# Pro_Trinket_Keyboard.net
KiCad netlist of a schematic drawn in EAGLE
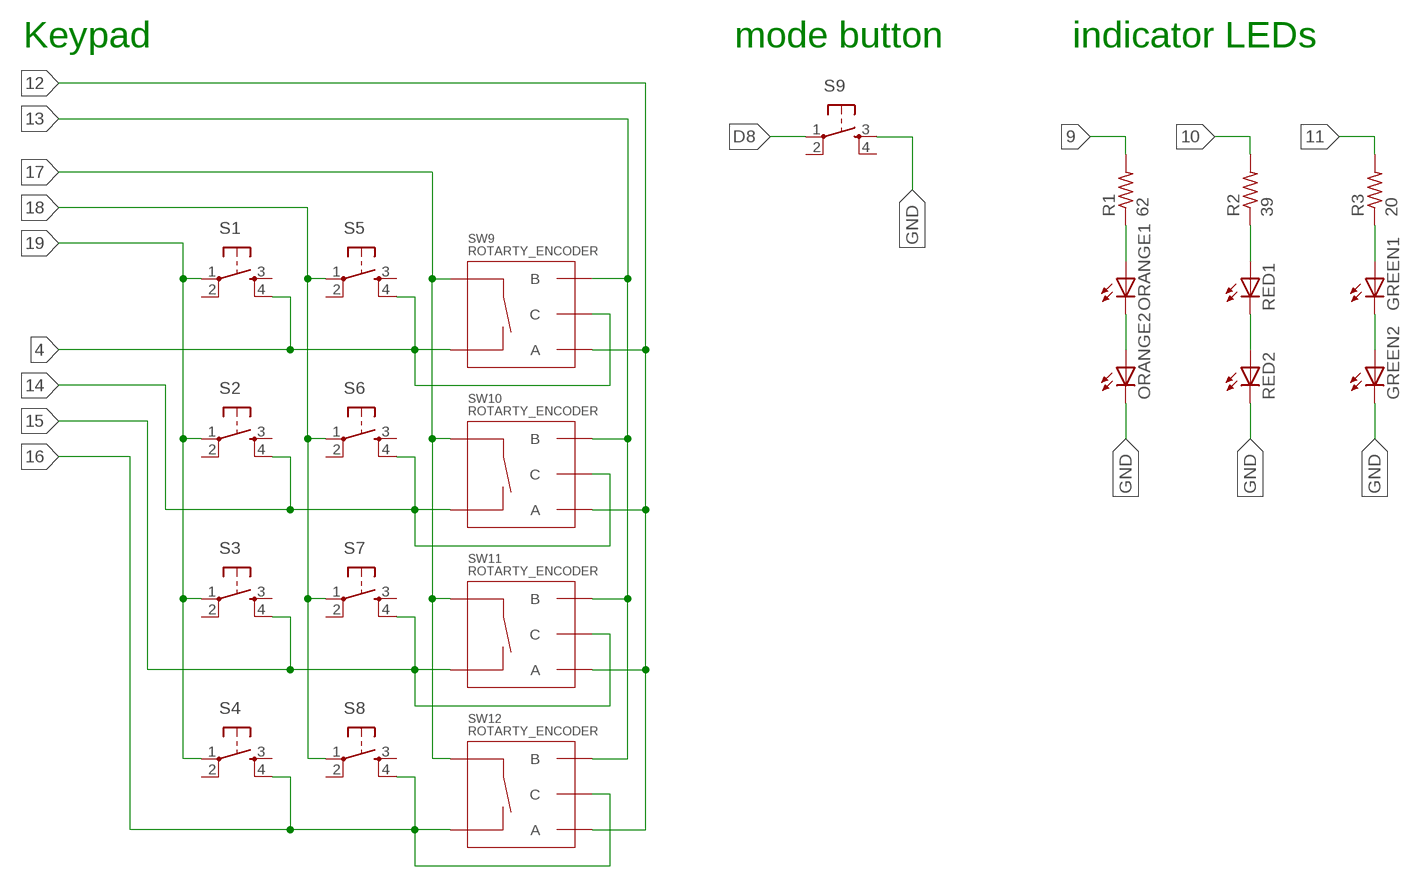
[diagram p0: schematic, sheet 1]

(export (version "E")
  (design (tool "Eeschema 10.0.6"))
  (components
    (comp (ref "GREEN1")
      (value "LED3MM")
      (footprint "eagle-import:LED3MM")
      (libsource (lib "eagle-import") (part "LED3MM"))
    )
    (comp (ref "GREEN2")
      (value "LED3MM")
      (footprint "eagle-import:LED3MM")
      (libsource (lib "eagle-import") (part "LED3MM"))
    )
    (comp (ref "ORANGE1")
      (value "LED3MM")
      (footprint "eagle-import:LED3MM")
      (libsource (lib "eagle-import") (part "LED3MM"))
    )
    (comp (ref "ORANGE2")
      (value "LED3MM")
      (footprint "eagle-import:LED3MM")
      (libsource (lib "eagle-import") (part "LED3MM"))
    )
    (comp (ref "R1")
      (value "62")
      (footprint "eagle-import:0204_7")
      (libsource (lib "eagle-import") (part "R-US_0204/7"))
    )
    (comp (ref "R2")
      (value "39")
      (footprint "eagle-import:0204_7")
      (libsource (lib "eagle-import") (part "R-US_0204/7"))
    )
    (comp (ref "R3")
      (value "20")
      (footprint "eagle-import:0204_7")
      (libsource (lib "eagle-import") (part "R-US_0204/7"))
    )
    (comp (ref "RED1")
      (value "LED3MM")
      (footprint "eagle-import:LED3MM")
      (libsource (lib "eagle-import") (part "LED3MM"))
    )
    (comp (ref "RED2")
      (value "LED3MM")
      (footprint "eagle-import:LED3MM")
      (libsource (lib "eagle-import") (part "LED3MM"))
    )
    (comp (ref "S1")
      (value "TAC_SWITCHPTH")
      (footprint "eagle-import:TACTILE-PTH")
      (libsource (lib "eagle-import") (part "TAC_SWITCHPTH"))
    )
    (comp (ref "S2")
      (value "TAC_SWITCHPTH")
      (footprint "eagle-import:TACTILE-PTH")
      (libsource (lib "eagle-import") (part "TAC_SWITCHPTH"))
    )
    (comp (ref "S3")
      (value "TAC_SWITCHPTH")
      (footprint "eagle-import:TACTILE-PTH")
      (libsource (lib "eagle-import") (part "TAC_SWITCHPTH"))
    )
    (comp (ref "S4")
      (value "TAC_SWITCHPTH")
      (footprint "eagle-import:TACTILE-PTH")
      (libsource (lib "eagle-import") (part "TAC_SWITCHPTH"))
    )
    (comp (ref "S5")
      (value "TAC_SWITCHPTH")
      (footprint "eagle-import:TACTILE-PTH")
      (libsource (lib "eagle-import") (part "TAC_SWITCHPTH"))
    )
    (comp (ref "S6")
      (value "TAC_SWITCHPTH")
      (footprint "eagle-import:TACTILE-PTH")
      (libsource (lib "eagle-import") (part "TAC_SWITCHPTH"))
    )
    (comp (ref "S7")
      (value "TAC_SWITCHPTH")
      (footprint "eagle-import:TACTILE-PTH")
      (libsource (lib "eagle-import") (part "TAC_SWITCHPTH"))
    )
    (comp (ref "S8")
      (value "TAC_SWITCHPTH")
      (footprint "eagle-import:TACTILE-PTH")
      (libsource (lib "eagle-import") (part "TAC_SWITCHPTH"))
    )
    (comp (ref "S9")
      (value "TAC_SWITCHPTH")
      (footprint "eagle-import:TACTILE-PTH")
      (libsource (lib "eagle-import") (part "TAC_SWITCHPTH"))
    )
    (comp (ref "SW9")
      (value "ROTARTY_ENCODER")
      (footprint "eagle-import:ROTARY_ENC_PLAIN")
      (libsource (lib "eagle-import") (part "ROTARTY_ENCODER"))
    )
    (comp (ref "SW10")
      (value "ROTARTY_ENCODER")
      (footprint "eagle-import:ROTARY_ENC_PLAIN")
      (libsource (lib "eagle-import") (part "ROTARTY_ENCODER"))
    )
    (comp (ref "SW11")
      (value "ROTARTY_ENCODER")
      (footprint "eagle-import:ROTARY_ENC_PLAIN")
      (libsource (lib "eagle-import") (part "ROTARTY_ENCODER"))
    )
    (comp (ref "SW12")
      (value "ROTARTY_ENCODER")
      (footprint "eagle-import:ROTARY_ENC_PLAIN")
      (libsource (lib "eagle-import") (part "ROTARTY_ENCODER"))
    )
  )
  (nets
    (net (code "1") (name "4") (class "Default")
      (node (ref "S1") (pin "4") (pinfunction "4_4") (pintype "passive"))
      (node (ref "S5") (pin "4") (pinfunction "4_4") (pintype "passive"))
      (node (ref "SW9") (pin "C") (pinfunction "C_C") (pintype "bidirectional"))
      (node (ref "SW9") (pin "SW-") (pinfunction "SW-_SW-") (pintype "bidirectional"))
    )
    (net (code "2") (name "9") (class "Default")
      (node (ref "R1") (pin "2") (pinfunction "2_2") (pintype "passive"))
    )
    (net (code "3") (name "10") (class "Default")
      (node (ref "R2") (pin "2") (pinfunction "2_2") (pintype "passive"))
    )
    (net (code "4") (name "11") (class "Default")
      (node (ref "R3") (pin "2") (pinfunction "2_2") (pintype "passive"))
    )
    (net (code "5") (name "12") (class "Default")
      (node (ref "SW10") (pin "A") (pinfunction "A_A") (pintype "bidirectional"))
      (node (ref "SW11") (pin "A") (pinfunction "A_A") (pintype "bidirectional"))
      (node (ref "SW12") (pin "A") (pinfunction "A_A") (pintype "bidirectional"))
      (node (ref "SW9") (pin "A") (pinfunction "A_A") (pintype "bidirectional"))
    )
    (net (code "6") (name "13") (class "Default")
      (node (ref "SW10") (pin "B") (pinfunction "B_B") (pintype "bidirectional"))
      (node (ref "SW11") (pin "B") (pinfunction "B_B") (pintype "bidirectional"))
      (node (ref "SW12") (pin "B") (pinfunction "B_B") (pintype "bidirectional"))
      (node (ref "SW9") (pin "B") (pinfunction "B_B") (pintype "bidirectional"))
    )
    (net (code "7") (name "14") (class "Default")
      (node (ref "S2") (pin "4") (pinfunction "4_4") (pintype "passive"))
      (node (ref "S6") (pin "4") (pinfunction "4_4") (pintype "passive"))
      (node (ref "SW10") (pin "C") (pinfunction "C_C") (pintype "bidirectional"))
      (node (ref "SW10") (pin "SW-") (pinfunction "SW-_SW-") (pintype "bidirectional"))
    )
    (net (code "8") (name "15") (class "Default")
      (node (ref "S3") (pin "4") (pinfunction "4_4") (pintype "passive"))
      (node (ref "S7") (pin "4") (pinfunction "4_4") (pintype "passive"))
      (node (ref "SW11") (pin "C") (pinfunction "C_C") (pintype "bidirectional"))
      (node (ref "SW11") (pin "SW-") (pinfunction "SW-_SW-") (pintype "bidirectional"))
    )
    (net (code "9") (name "16") (class "Default")
      (node (ref "S4") (pin "4") (pinfunction "4_4") (pintype "passive"))
      (node (ref "S8") (pin "4") (pinfunction "4_4") (pintype "passive"))
      (node (ref "SW12") (pin "C") (pinfunction "C_C") (pintype "bidirectional"))
      (node (ref "SW12") (pin "SW-") (pinfunction "SW-_SW-") (pintype "bidirectional"))
    )
    (net (code "10") (name "17") (class "Default")
      (node (ref "SW10") (pin "SW+") (pinfunction "SW+_SW+") (pintype "bidirectional"))
      (node (ref "SW11") (pin "SW+") (pinfunction "SW+_SW+") (pintype "bidirectional"))
      (node (ref "SW12") (pin "SW+") (pinfunction "SW+_SW+") (pintype "bidirectional"))
      (node (ref "SW9") (pin "SW+") (pinfunction "SW+_SW+") (pintype "bidirectional"))
    )
    (net (code "11") (name "18") (class "Default")
      (node (ref "S5") (pin "1") (pinfunction "1_1") (pintype "passive"))
      (node (ref "S6") (pin "1") (pinfunction "1_1") (pintype "passive"))
      (node (ref "S7") (pin "1") (pinfunction "1_1") (pintype "passive"))
      (node (ref "S8") (pin "1") (pinfunction "1_1") (pintype "passive"))
    )
    (net (code "12") (name "19") (class "Default")
      (node (ref "S1") (pin "1") (pinfunction "1_1") (pintype "passive"))
      (node (ref "S2") (pin "1") (pinfunction "1_1") (pintype "passive"))
      (node (ref "S3") (pin "1") (pinfunction "1_1") (pintype "passive"))
      (node (ref "S4") (pin "1") (pinfunction "1_1") (pintype "passive"))
    )
    (net (code "13") (name "D8") (class "Default")
      (node (ref "S9") (pin "1") (pinfunction "1_1") (pintype "passive"))
    )
    (net (code "14") (name "GND") (class "Default")
      (node (ref "GREEN2") (pin "K") (pinfunction "C_K") (pintype "passive"))
      (node (ref "ORANGE2") (pin "K") (pinfunction "C_K") (pintype "passive"))
      (node (ref "RED2") (pin "K") (pinfunction "C_K") (pintype "passive"))
      (node (ref "S9") (pin "3") (pinfunction "3_3") (pintype "passive"))
    )
    (net (code "15") (name "Net-(GREEN1-C)") (class "Default")
      (node (ref "GREEN1") (pin "K") (pinfunction "C_K") (pintype "passive"))
      (node (ref "GREEN2") (pin "A") (pinfunction "A_A") (pintype "passive"))
    )
    (net (code "16") (name "Net-(GREEN1-PadA)") (class "Default")
      (node (ref "GREEN1") (pin "A") (pinfunction "A_A") (pintype "passive"))
      (node (ref "R3") (pin "1") (pinfunction "1_1") (pintype "passive"))
    )
    (net (code "17") (name "Net-(ORANGE1-C)") (class "Default")
      (node (ref "ORANGE1") (pin "K") (pinfunction "C_K") (pintype "passive"))
      (node (ref "ORANGE2") (pin "A") (pinfunction "A_A") (pintype "passive"))
    )
    (net (code "18") (name "Net-(ORANGE1-PadA)") (class "Default")
      (node (ref "ORANGE1") (pin "A") (pinfunction "A_A") (pintype "passive"))
      (node (ref "R1") (pin "1") (pinfunction "1_1") (pintype "passive"))
    )
    (net (code "19") (name "Net-(R2-Pad1)") (class "Default")
      (node (ref "R2") (pin "1") (pinfunction "1_1") (pintype "passive"))
      (node (ref "RED1") (pin "A") (pinfunction "A_A") (pintype "passive"))
    )
    (net (code "20") (name "Net-(RED1-C)") (class "Default")
      (node (ref "RED1") (pin "K") (pinfunction "C_K") (pintype "passive"))
      (node (ref "RED2") (pin "A") (pinfunction "A_A") (pintype "passive"))
    )
    (net (code "21") (name "unconnected-(S1-Pad2)") (class "Default")
      (node (ref "S1") (pin "2") (pinfunction "2_2") (pintype "passive"))
    )
    (net (code "22") (name "unconnected-(S1-Pad3)") (class "Default")
      (node (ref "S1") (pin "3") (pinfunction "3_3") (pintype "passive"))
    )
    (net (code "23") (name "unconnected-(S2-Pad2)") (class "Default")
      (node (ref "S2") (pin "2") (pinfunction "2_2") (pintype "passive"))
    )
    (net (code "24") (name "unconnected-(S2-Pad3)") (class "Default")
      (node (ref "S2") (pin "3") (pinfunction "3_3") (pintype "passive"))
    )
    (net (code "25") (name "unconnected-(S3-Pad2)") (class "Default")
      (node (ref "S3") (pin "2") (pinfunction "2_2") (pintype "passive"))
    )
    (net (code "26") (name "unconnected-(S3-Pad3)") (class "Default")
      (node (ref "S3") (pin "3") (pinfunction "3_3") (pintype "passive"))
    )
    (net (code "27") (name "unconnected-(S4-Pad2)") (class "Default")
      (node (ref "S4") (pin "2") (pinfunction "2_2") (pintype "passive"))
    )
    (net (code "28") (name "unconnected-(S4-Pad3)") (class "Default")
      (node (ref "S4") (pin "3") (pinfunction "3_3") (pintype "passive"))
    )
    (net (code "29") (name "unconnected-(S5-Pad2)") (class "Default")
      (node (ref "S5") (pin "2") (pinfunction "2_2") (pintype "passive"))
    )
    (net (code "30") (name "unconnected-(S5-Pad3)") (class "Default")
      (node (ref "S5") (pin "3") (pinfunction "3_3") (pintype "passive"))
    )
    (net (code "31") (name "unconnected-(S6-Pad2)") (class "Default")
      (node (ref "S6") (pin "2") (pinfunction "2_2") (pintype "passive"))
    )
    (net (code "32") (name "unconnected-(S6-Pad3)") (class "Default")
      (node (ref "S6") (pin "3") (pinfunction "3_3") (pintype "passive"))
    )
    (net (code "33") (name "unconnected-(S7-Pad2)") (class "Default")
      (node (ref "S7") (pin "2") (pinfunction "2_2") (pintype "passive"))
    )
    (net (code "34") (name "unconnected-(S7-Pad3)") (class "Default")
      (node (ref "S7") (pin "3") (pinfunction "3_3") (pintype "passive"))
    )
    (net (code "35") (name "unconnected-(S8-Pad2)") (class "Default")
      (node (ref "S8") (pin "2") (pinfunction "2_2") (pintype "passive"))
    )
    (net (code "36") (name "unconnected-(S8-Pad3)") (class "Default")
      (node (ref "S8") (pin "3") (pinfunction "3_3") (pintype "passive"))
    )
    (net (code "37") (name "unconnected-(S9-Pad2)") (class "Default")
      (node (ref "S9") (pin "2") (pinfunction "2_2") (pintype "passive"))
    )
    (net (code "38") (name "unconnected-(S9-Pad4)") (class "Default")
      (node (ref "S9") (pin "4") (pinfunction "4_4") (pintype "passive"))
    )
  )
)
